# FAE_V2_1.net
KiCad netlist of a schematic drawn in EAGLE
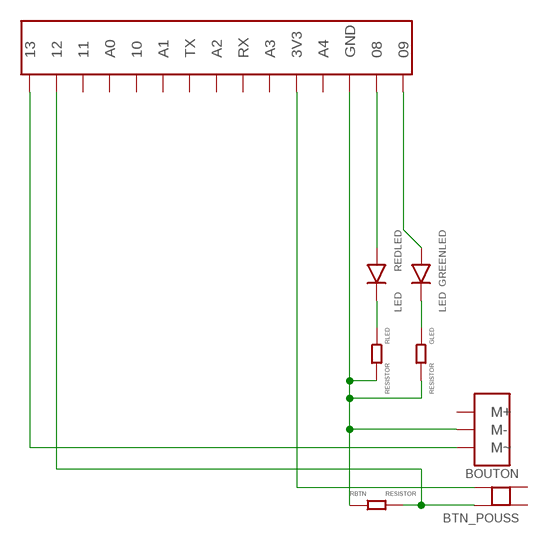
[diagram p0: schematic, sheet 1]

(export (version "E")
  (design (tool "Eeschema 10.0.6"))
  (components
    (comp (ref "BTN_POUSS")
      (value "BOUTON")
      (footprint "eagle-import:BOUTON")
      (libsource (lib "eagle-import") (part "BOUTON"))
    )
    (comp (ref "GLED")
      (value "RESISTOR")
      (footprint "eagle-import:RESISTOR")
      (libsource (lib "eagle-import") (part "RESISTOR"))
    )
    (comp (ref "GREENLED")
      (value "LED")
      (footprint "eagle-import:LED")
      (libsource (lib "eagle-import") (part "LED"))
    )
    (comp (ref "RBTN")
      (value "RESISTOR")
      (footprint "eagle-import:RESISTOR")
      (libsource (lib "eagle-import") (part "RESISTOR"))
    )
    (comp (ref "REDLED")
      (value "LED")
      (footprint "eagle-import:LED")
      (libsource (lib "eagle-import") (part "LED"))
    )
    (comp (ref "RLED")
      (value "RESISTOR")
      (footprint "eagle-import:RESISTOR")
      (libsource (lib "eagle-import") (part "RESISTOR"))
    )
    (comp (ref "U$1")
      (value "RAZOR_BOARD")
      (footprint "eagle-import:RAZOR_BOARD")
      (libsource (lib "eagle-import") (part "RAZOR_BOARD"))
    )
    (comp (ref "U$3")
      (value "SERVO_ADAPT")
      (footprint "eagle-import:SERVO_ADAPT")
      (libsource (lib "eagle-import") (part "SERVO_ADAPT"))
    )
  )
  (nets
    (net (code "1") (name "Net-(BTN_POUSS-PadC)") (class "Default")
      (node (ref "BTN_POUSS") (pin "C") (pinfunction "C_C") (pintype "bidirectional"))
      (node (ref "RBTN") (pin "B") (pinfunction "B_B") (pintype "bidirectional"))
      (node (ref "U$1") (pin "12") (pinfunction "12_12") (pintype "bidirectional"))
    )
    (net (code "2") (name "Net-(BTN_POUSS-PadD)") (class "Default")
      (node (ref "BTN_POUSS") (pin "D") (pinfunction "D_D") (pintype "bidirectional"))
      (node (ref "U$1") (pin "3V3") (pinfunction "3V3_3V3") (pintype "bidirectional"))
    )
    (net (code "3") (name "Net-(GLED-PadA)") (class "Default")
      (node (ref "GLED") (pin "A") (pinfunction "A_A") (pintype "bidirectional"))
      (node (ref "GREENLED") (pin "OUT") (pinfunction "OUT_OUT") (pintype "output"))
    )
    (net (code "4") (name "Net-(GLED-PadB)") (class "Default")
      (node (ref "GLED") (pin "B") (pinfunction "B_B") (pintype "bidirectional"))
      (node (ref "RBTN") (pin "A") (pinfunction "A_A") (pintype "bidirectional"))
      (node (ref "RLED") (pin "B") (pinfunction "B_B") (pintype "bidirectional"))
      (node (ref "U$1") (pin "GND") (pinfunction "GND_GND") (pintype "bidirectional"))
      (node (ref "U$3") (pin "M-") (pinfunction "M-_M-") (pintype "bidirectional"))
    )
    (net (code "5") (name "Net-(GREENLED-PadIN)") (class "Default")
      (node (ref "GREENLED") (pin "IN") (pinfunction "IN_IN") (pintype "input"))
      (node (ref "U$1") (pin "09") (pinfunction "09_09") (pintype "bidirectional"))
    )
    (net (code "6") (name "Net-(REDLED-PadIN)") (class "Default")
      (node (ref "REDLED") (pin "IN") (pinfunction "IN_IN") (pintype "input"))
      (node (ref "U$1") (pin "08") (pinfunction "08_08") (pintype "bidirectional"))
    )
    (net (code "7") (name "Net-(REDLED-PadOUT)") (class "Default")
      (node (ref "REDLED") (pin "OUT") (pinfunction "OUT_OUT") (pintype "output"))
      (node (ref "RLED") (pin "A") (pinfunction "A_A") (pintype "bidirectional"))
    )
    (net (code "8") (name "Net-(U$3-M~{})") (class "Default")
      (node (ref "U$1") (pin "13") (pinfunction "13_13") (pintype "bidirectional"))
      (node (ref "U$3") (pin "M~") (pinfunction "M~{}_M~") (pintype "bidirectional"))
    )
    (net (code "9") (name "unconnected-(BTN_POUSS-PadA)") (class "Default")
      (node (ref "BTN_POUSS") (pin "A") (pinfunction "A_A") (pintype "bidirectional"))
    )
    (net (code "10") (name "unconnected-(BTN_POUSS-PadB)") (class "Default")
      (node (ref "BTN_POUSS") (pin "B") (pinfunction "B_B") (pintype "bidirectional"))
    )
    (net (code "11") (name "unconnected-(U$1-Pad10)") (class "Default")
      (node (ref "U$1") (pin "10") (pinfunction "10_10") (pintype "bidirectional"))
    )
    (net (code "12") (name "unconnected-(U$1-Pad11)") (class "Default")
      (node (ref "U$1") (pin "11") (pinfunction "11_11") (pintype "bidirectional"))
    )
    (net (code "13") (name "unconnected-(U$1-PadA0)") (class "Default")
      (node (ref "U$1") (pin "A0") (pinfunction "A0_A0") (pintype "bidirectional"))
    )
    (net (code "14") (name "unconnected-(U$1-PadA1)") (class "Default")
      (node (ref "U$1") (pin "A1") (pinfunction "A1_A1") (pintype "bidirectional"))
    )
    (net (code "15") (name "unconnected-(U$1-PadA2)") (class "Default")
      (node (ref "U$1") (pin "A2") (pinfunction "A2_A2") (pintype "bidirectional"))
    )
    (net (code "16") (name "unconnected-(U$1-PadA3)") (class "Default")
      (node (ref "U$1") (pin "A3") (pinfunction "A3_A3") (pintype "bidirectional"))
    )
    (net (code "17") (name "unconnected-(U$1-PadA4)") (class "Default")
      (node (ref "U$1") (pin "A4") (pinfunction "A4_A4") (pintype "bidirectional"))
    )
    (net (code "18") (name "unconnected-(U$1-PadRX)") (class "Default")
      (node (ref "U$1") (pin "RX") (pinfunction "RX_RX") (pintype "bidirectional"))
    )
    (net (code "19") (name "unconnected-(U$1-PadTX)") (class "Default")
      (node (ref "U$1") (pin "TX") (pinfunction "TX_TX") (pintype "bidirectional"))
    )
    (net (code "20") (name "unconnected-(U$3-PadM+)") (class "Default")
      (node (ref "U$3") (pin "M+") (pinfunction "M+_M+") (pintype "bidirectional"))
    )
  )
)
